# BQ24073.net
KiCad netlist of a schematic drawn in Altium Designer
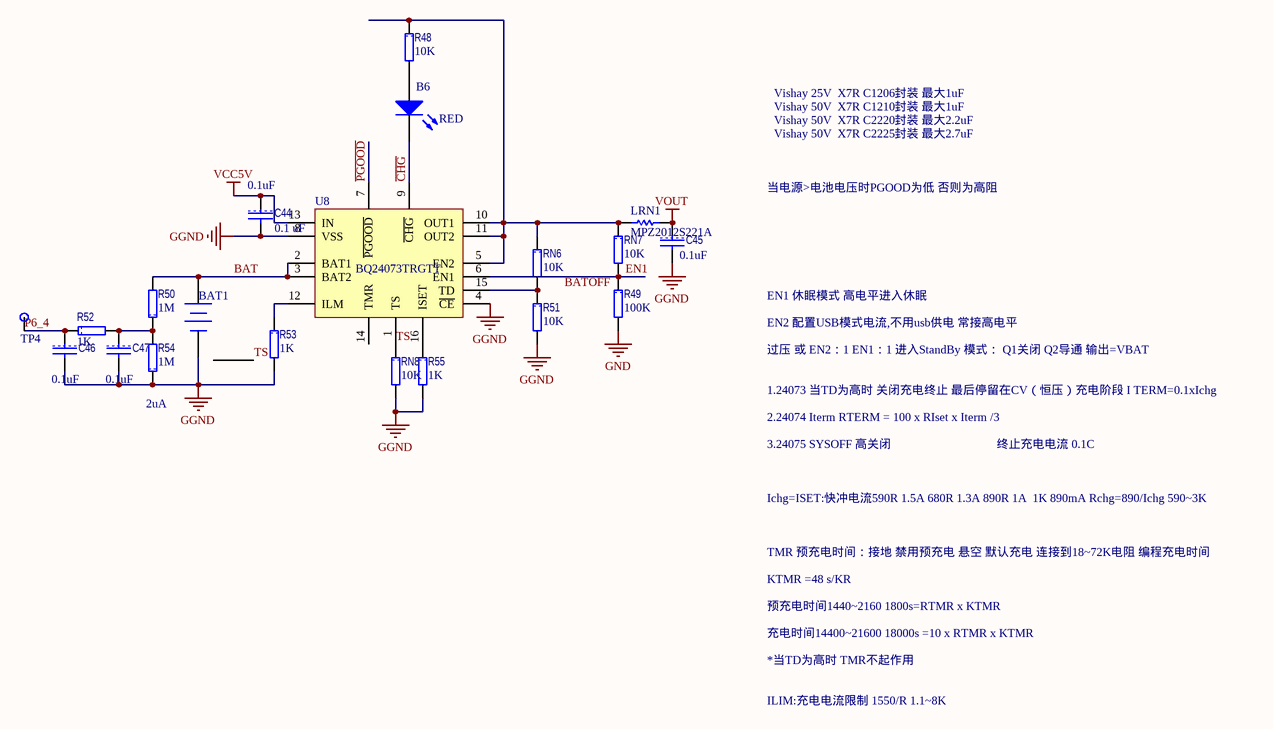
[diagram p0: BQ24073_锂电池充电.SchDoc]

(export (version "E")
  (design (tool "Eeschema 10.0.6"))
  (components
    (comp (ref "B6")
      (value "RED")
      (footprint "0805LED")
      (description "Typical RED, GREEN, YELLOW, AMBER GaAs LED")
      (fields (field (name "PUBLISHER") "Altium Limited"))
      (libsource (lib "Miscellaneous Devices") (part "LED2"))
    )
    (comp (ref "BAT1")
      (value "18650/5000mAH/3.7V")
      (footprint "BAT_3")
      (description "插针 Multicell Battery")
      (libsource (lib "*") (part "Battery"))
    )
    (comp (ref "C44")
      (value "0.1uF")
      (footprint "1608[0603]C")
      (description "多层陶瓷电容器MLCC - SMD/SMT 0603 0.1uF 50volts X7R 10%")
      (fields
        (field (name "MANUFACTURER") "TDK")
        (field (name "MANUFACTURER PART NUMBER") "C1608X7R1H104K")
        (field (name "ΜÇÈÝ") "0.1 uF")
      )
      (libsource (lib "*") (part "CAP"))
    )
    (comp (ref "C45")
      (value "0.1uF")
      (footprint "1608[0603]C")
      (description "多层陶瓷电容器MLCC - SMD/SMT 0603 0.1uF 50volts X7R 10%")
      (fields (field (name "MANUFACTURER") "TDK") (field (name "MANUFACTURER PART NUMBER") "C1608X7R1H104K"))
      (libsource (lib "*") (part "CAP"))
    )
    (comp (ref "C46")
      (value "0.1uF")
      (footprint "1608[0603]C")
      (description "多层陶瓷电容器MLCC - SMD/SMT 0603 0.1uF 50volts X7R 10%")
      (fields (field (name "MANUFACTURER") "TDK") (field (name "MANUFACTURER PART NUMBER") "C1608X7R1H104K"))
      (libsource (lib "*") (part "CAP"))
    )
    (comp (ref "C47")
      (value "0.1uF")
      (footprint "1608[0603]C")
      (description "多层陶瓷电容器MLCC - SMD/SMT 0603 0.1uF 50volts X7R 10%")
      (fields (field (name "MANUFACTURER") "TDK") (field (name "MANUFACTURER PART NUMBER") "C1608X7R1H104K"))
      (libsource (lib "*") (part "CAP"))
    )
    (comp (ref "LRN1")
      (value "MPZ2012S221A")
      (footprint "2012[0805]")
      (description "电磁干扰滤波珠子、扼流圈和阵列 Ferrite Chip Beads")
      (fields (field (name "MANUFACTURER") "TDK"))
      (libsource (lib "Miscellaneous Devices") (part "Res Semi"))
    )
    (comp (ref "R48")
      (value "10K")
      (footprint "1608[0603]R")
      (description "厚膜电阻器 - SMD 1/10watt 10Kohms 1%")
      (fields
        (field (name "MANUFACTURER") "Vishay / Dale")
        (field (name "MANUFACTURER PART NUMBER") "CRCW060310K0FKEA")
      )
      (libsource (lib "10K 1%") (part "RES"))
    )
    (comp (ref "R49")
      (value "100K")
      (footprint "1608[0603]R")
      (description "厚膜电阻器 - SMD 1/10watt 100Kohms 1%")
      (fields
        (field (name "MANUFACTURER") "Vishay / Dale")
        (field (name "MANUFACTURER PART NUMBER") "CRCW0603100KFKEA")
      )
      (libsource (lib "100K 1%") (part "RES"))
    )
    (comp (ref "R50")
      (value "1M")
      (footprint "1608[0603]R")
      (description "厚膜电阻器 - SMD 1/10watt 1.0Mohms 1%")
      (fields
        (field (name "MANUFACTURER") "Vishay / Dale")
        (field (name "MANUFACTURER PART NUMBER") "CRCW06031M00FKEA")
      )
      (libsource (lib "1M 1%") (part "RES"))
    )
    (comp (ref "R51")
      (value "10K")
      (footprint "1608[0603]R")
      (description "厚膜电阻器 - SMD 1/10watt 10Kohms 1%")
      (fields
        (field (name "MANUFACTURER") "Vishay / Dale")
        (field (name "MANUFACTURER PART NUMBER") "CRCW060310K0FKEA")
      )
      (libsource (lib "10K 1%") (part "RES"))
    )
    (comp (ref "R52")
      (value "1K")
      (footprint "1608[0603]R")
      (description "厚膜电阻器 - SMD 1/10watt 1.0Kohms 1%")
      (fields
        (field (name "MANUFACTURER") "Vishay / Dale")
        (field (name "MANUFACTURER PART NUMBER") "CRCW06031K00FKEA")
      )
      (libsource (lib "1K 1%") (part "RES"))
    )
    (comp (ref "R53")
      (value "1K")
      (footprint "1608[0603]R")
      (description "厚膜电阻器 - SMD 1/10watt 1.0Kohms 1%")
      (fields
        (field (name "MANUFACTURER") "Vishay / Dale")
        (field (name "MANUFACTURER PART NUMBER") "CRCW06031K00FKEA")
      )
      (libsource (lib "1K 1%") (part "RES"))
    )
    (comp (ref "R54")
      (value "1M")
      (footprint "1608[0603]R")
      (description "厚膜电阻器 - SMD 1/10watt 1.0Mohms 1%")
      (fields
        (field (name "MANUFACTURER") "Vishay / Dale")
        (field (name "MANUFACTURER PART NUMBER") "CRCW06031M00FKEA")
      )
      (libsource (lib "1M 1%") (part "RES"))
    )
    (comp (ref "R55")
      (value "1K")
      (footprint "1608[0603]R")
      (description "厚膜电阻器 - SMD 1/10watt 1.0Kohms 1%")
      (fields
        (field (name "MANUFACTURER") "Vishay / Dale")
        (field (name "MANUFACTURER PART NUMBER") "CRCW06031K00FKEA")
      )
      (libsource (lib "1K 1%") (part "RES"))
    )
    (comp (ref "RN6")
      (value "10K")
      (footprint "1608[0603]RN")
      (description "厚膜电阻器 - SMD 1/10watt 10Kohms 1%")
      (fields
        (field (name "MANUFACTURER") "Vishay / Dale")
        (field (name "MANUFACTURER PART NUMBER") "CRCW060310K0FKEA")
      )
      (libsource (lib "10K 1%") (part "RES"))
    )
    (comp (ref "RN7")
      (value "10K")
      (footprint "1608[0603]RN")
      (description "厚膜电阻器 - SMD 1/10watt 10Kohms 1%")
      (fields
        (field (name "MANUFACTURER") "Vishay / Dale")
        (field (name "MANUFACTURER PART NUMBER") "CRCW060310K0FKEA")
      )
      (libsource (lib "10K 1%") (part "RES"))
    )
    (comp (ref "RN8")
      (value "10K")
      (footprint "1608[0603]RN")
      (description "厚膜电阻器 - SMD 1/10watt 10Kohms 1%")
      (fields
        (field (name "MANUFACTURER") "Vishay / Dale")
        (field (name "MANUFACTURER PART NUMBER") "CRCW060310K0FKEA")
      )
      (libsource (lib "10K 1%") (part "RES"))
    )
    (comp (ref "TP4")
      (value "TP")
      (footprint "TP")
      (description "Test Point")
      (libsource (lib "S3C2440V9") (part "Test Point"))
    )
    (comp (ref "U8")
      (value "BQ24073TRGTT")
      (footprint "BQ24073")
      (description "电池管理 1.5A USB-Friendly Li Ion Batt Charger")
      (fields
        (field (name "MANUFACTURER") "Texas Instruments")
        (field (name "MANUFACTURER PART NUMBER") "BQ24075TRGTT")
      )
      (libsource (lib "*") (part "BQ24073"))
    )
  )
  (nets
    (net (code "1") (name "/BAT") (class "Default")
      (node (ref "BAT1") (pin "1") (pinfunction "+_1") (pintype "passive"))
      (node (ref "R50") (pin "2") (pinfunction "2_2") (pintype "passive"))
      (node (ref "U8") (pin "2") (pinfunction "BAT1_2") (pintype "passive"))
      (node (ref "U8") (pin "3") (pinfunction "BAT2_3") (pintype "passive"))
    )
    (net (code "3") (name "/EN1") (class "Default")
      (node (ref "R49") (pin "1") (pinfunction "1_1") (pintype "passive"))
      (node (ref "RN7") (pin "2") (pinfunction "2_2") (pintype "passive"))
      (node (ref "U8") (pin "6") (pinfunction "EN1_6") (pintype "passive"))
    )
    (net (code "4") (name "/P6_4") (class "Default")
      (node (ref "C46") (pin "1") (pinfunction "1_1") (pintype "passive"))
      (node (ref "R52") (pin "1") (pinfunction "1_1") (pintype "passive"))
      (node (ref "TP4") (pin "1") (pinfunction "TestPoint_1") (pintype "passive"))
    )
    (net (code "5") (name "/TS") (class "Default")
      (node (ref "BAT1") (pin "3") (pinfunction "TS_3") (pintype "passive"))
      (node (ref "RN8") (pin "1") (pinfunction "1_1") (pintype "passive"))
      (node (ref "U8") (pin "1") (pinfunction "TS_1") (pintype "passive"))
    )
    (net (code "6") (name "/~{CHG}") (class "Default")
      (node (ref "B6") (pin "2") (pinfunction "K_2") (pintype "passive"))
      (node (ref "U8") (pin "9") (pinfunction "~{CHG}_9") (pintype "passive"))
    )
    (net (code "7") (name "/~{PGOOD}") (class "Default")
      (node (ref "U8") (pin "7") (pinfunction "~{PGOOD}_7") (pintype "passive"))
    )
    (net (code "8") (name "GGND") (class "Default")
      (node (ref "BAT1") (pin "2") (pinfunction "-_2") (pintype "passive"))
      (node (ref "C44") (pin "2") (pinfunction "2_2") (pintype "passive"))
      (node (ref "C45") (pin "2") (pinfunction "2_2") (pintype "passive"))
      (node (ref "C46") (pin "2") (pinfunction "2_2") (pintype "passive"))
      (node (ref "C47") (pin "2") (pinfunction "2_2") (pintype "passive"))
      (node (ref "R51") (pin "2") (pinfunction "2_2") (pintype "passive"))
      (node (ref "R53") (pin "2") (pinfunction "2_2") (pintype "passive"))
      (node (ref "R54") (pin "1") (pinfunction "1_1") (pintype "passive"))
      (node (ref "R55") (pin "2") (pinfunction "2_2") (pintype "passive"))
      (node (ref "RN8") (pin "2") (pinfunction "2_2") (pintype "passive"))
      (node (ref "U8") (pin "4") (pinfunction "~{CE}_4") (pintype "passive"))
      (node (ref "U8") (pin "8") (pinfunction "VSS_8") (pintype "passive"))
    )
    (net (code "9") (name "GND") (class "Default")
      (node (ref "R49") (pin "2") (pinfunction "2_2") (pintype "passive"))
    )
    (net (code "10") (name "Net-(B6-A)") (class "Default")
      (node (ref "B6") (pin "1") (pinfunction "A_1") (pintype "passive"))
      (node (ref "R48") (pin "2") (pinfunction "2_2") (pintype "passive"))
    )
    (net (code "11") (name "Net-(C47-Pad1)") (class "Default")
      (node (ref "C47") (pin "1") (pinfunction "1_1") (pintype "passive"))
      (node (ref "R50") (pin "1") (pinfunction "1_1") (pintype "passive"))
      (node (ref "R52") (pin "2") (pinfunction "2_2") (pintype "passive"))
      (node (ref "R54") (pin "2") (pinfunction "2_2") (pintype "passive"))
    )
    (net (code "12") (name "Net-(U8-EN2)") (class "Default")
      (node (ref "LRN1") (pin "1") (pinfunction "1_1") (pintype "passive"))
      (node (ref "R48") (pin "1") (pinfunction "1_1") (pintype "passive"))
      (node (ref "RN6") (pin "1") (pinfunction "1_1") (pintype "passive"))
      (node (ref "RN7") (pin "1") (pinfunction "1_1") (pintype "passive"))
      (node (ref "U8") (pin "10") (pinfunction "OUT1_10") (pintype "passive"))
      (node (ref "U8") (pin "11") (pinfunction "OUT2_11") (pintype "passive"))
      (node (ref "U8") (pin "5") (pinfunction "EN2_5") (pintype "passive"))
    )
    (net (code "13") (name "Net-(U8-ILM)") (class "Default")
      (node (ref "R53") (pin "1") (pinfunction "1_1") (pintype "passive"))
      (node (ref "U8") (pin "12") (pinfunction "ILM_12") (pintype "passive"))
    )
    (net (code "14") (name "Net-(U8-ISET)") (class "Default")
      (node (ref "R55") (pin "1") (pinfunction "1_1") (pintype "passive"))
      (node (ref "U8") (pin "16") (pinfunction "ISET_16") (pintype "passive"))
    )
    (net (code "15") (name "Net-(U8-TD)") (class "Default")
      (node (ref "R51") (pin "1") (pinfunction "1_1") (pintype "passive"))
      (node (ref "RN6") (pin "2") (pinfunction "2_2") (pintype "passive"))
      (node (ref "U8") (pin "15") (pinfunction "TD_15") (pintype "passive"))
    )
    (net (code "16") (name "VCC5V") (class "Default")
      (node (ref "C44") (pin "1") (pinfunction "1_1") (pintype "passive"))
      (node (ref "U8") (pin "13") (pinfunction "IN_13") (pintype "passive"))
    )
    (net (code "17") (name "VOUT") (class "Default")
      (node (ref "C45") (pin "1") (pinfunction "1_1") (pintype "passive"))
      (node (ref "LRN1") (pin "2") (pinfunction "2_2") (pintype "passive"))
    )
    (net (code "18") (name "unconnected-(U8-TMR-Pad14)") (class "Default")
      (node (ref "U8") (pin "14") (pinfunction "TMR_14") (pintype "passive"))
    )
  )
)
